# Power.net
KiCad netlist of a schematic drawn in Altium Designer
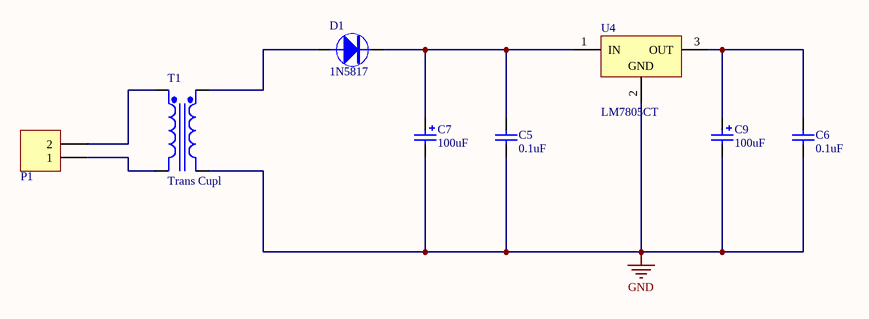
[diagram p0: Power.SchDoc]

(export (version "E")
  (design (tool "Eeschema 10.0.6"))
  (components
    (comp (ref "C5")
      (value "0.1uF")
      (footprint "RAD-0.2")
      (description "Capacitor")
      (fields (field (name "Comment") "Cap") (field (name "PUBLISHER") "Altium Limited"))
      (libsource (lib "TEST2024") (part "Cap"))
    )
    (comp (ref "C6")
      (value "0.1uF")
      (footprint "RAD-0.2")
      (description "Capacitor")
      (fields (field (name "Comment") "Cap") (field (name "PUBLISHER") "Altium Limited"))
      (libsource (lib "TEST2024") (part "Cap"))
    )
    (comp (ref "C7")
      (value "100uF")
      (footprint "RB7.6-15")
      (description "Polarized Capacitor (Radial)")
      (fields (field (name "Comment") "Cap Pol1") (field (name "PUBLISHER") "Altium Limited"))
      (libsource (lib "TEST2024") (part "Cap Pol1"))
    )
    (comp (ref "C9")
      (value "100uF")
      (footprint "RB7.6-15")
      (description "Polarized Capacitor (Radial)")
      (fields (field (name "Comment") "Cap Pol1") (field (name "PUBLISHER") "Altium Limited"))
      (libsource (lib "TEST2024") (part "Cap Pol1"))
    )
    (comp (ref "D1")
      (value "1N5817")
      (footprint "DO-15")
      (description "普通二极管")
      (libsource (lib "TEST2024") (part "1N5817"))
    )
    (comp (ref "P1")
      (value "Header 2")
      (footprint "HDR1X2")
      (description "Header, 2-Pin")
      (fields (field (name "PUBLISHER") "Altium Limited"))
      (libsource (lib "TEST2024") (part "Header 2"))
    )
    (comp (ref "T1")
      (value "Trans Cupl")
      (footprint "TRF_4")
      (description "Transformer (Coupled Inductor Model)")
      (fields (field (name "PUBLISHER") "Altium Limited"))
      (libsource (lib "TEST2024") (part "Trans Cupl"))
    )
    (comp (ref "U4")
      (value "LM7805CT")
      (footprint "T03B")
      (description "Series 3-Terminal Positive Regulator")
      (fields (field (name "PUBLISHER") "Altium Limited"))
      (libsource (lib "TEST2024") (part "LM7805CT"))
    )
  )
  (nets
    (net (code "1") (name "GND") (class "Default")
      (node (ref "C5") (pin "1") (pinfunction "1_1") (pintype "passive"))
      (node (ref "C6") (pin "1") (pinfunction "1_1") (pintype "passive"))
      (node (ref "C7") (pin "2") (pinfunction "2_2") (pintype "passive"))
      (node (ref "C9") (pin "2") (pinfunction "2_2") (pintype "passive"))
      (node (ref "T1") (pin "4") (pinfunction "Sec-_4") (pintype "passive"))
      (node (ref "U4") (pin "2") (pinfunction "GND_2") (pintype "power_in"))
    )
    (net (code "2") (name "Net-(T1-Pri+)") (class "Default")
      (node (ref "P1") (pin "2") (pinfunction "2_2") (pintype "passive"))
      (node (ref "T1") (pin "1") (pinfunction "Pri+_1") (pintype "passive"))
    )
    (net (code "3") (name "Net-(T1-Pri-)") (class "Default")
      (node (ref "P1") (pin "1") (pinfunction "1_1") (pintype "passive"))
      (node (ref "T1") (pin "2") (pinfunction "Pri-_2") (pintype "passive"))
    )
    (net (code "4") (name "Net-(T1-Sec+)") (class "Default")
      (node (ref "D1") (pin "A") (pinfunction "A_A") (pintype "passive"))
      (node (ref "T1") (pin "3") (pinfunction "Sec+_3") (pintype "passive"))
    )
    (net (code "5") (name "Net-(U4-IN)") (class "Default")
      (node (ref "C5") (pin "2") (pinfunction "2_2") (pintype "passive"))
      (node (ref "C7") (pin "1") (pinfunction "1_1") (pintype "passive"))
      (node (ref "D1") (pin "K") (pinfunction "K_K") (pintype "passive"))
      (node (ref "U4") (pin "1") (pinfunction "IN_1") (pintype "power_in"))
    )
    (net (code "6") (name "Net-(U4-OUT)") (class "Default")
      (node (ref "C6") (pin "2") (pinfunction "2_2") (pintype "passive"))
      (node (ref "C9") (pin "1") (pinfunction "1_1") (pintype "passive"))
      (node (ref "U4") (pin "3") (pinfunction "OUT_3") (pintype "power_in"))
    )
  )
)
